# V1_SENSOR.net
KiCad netlist of a schematic drawn in EAGLE
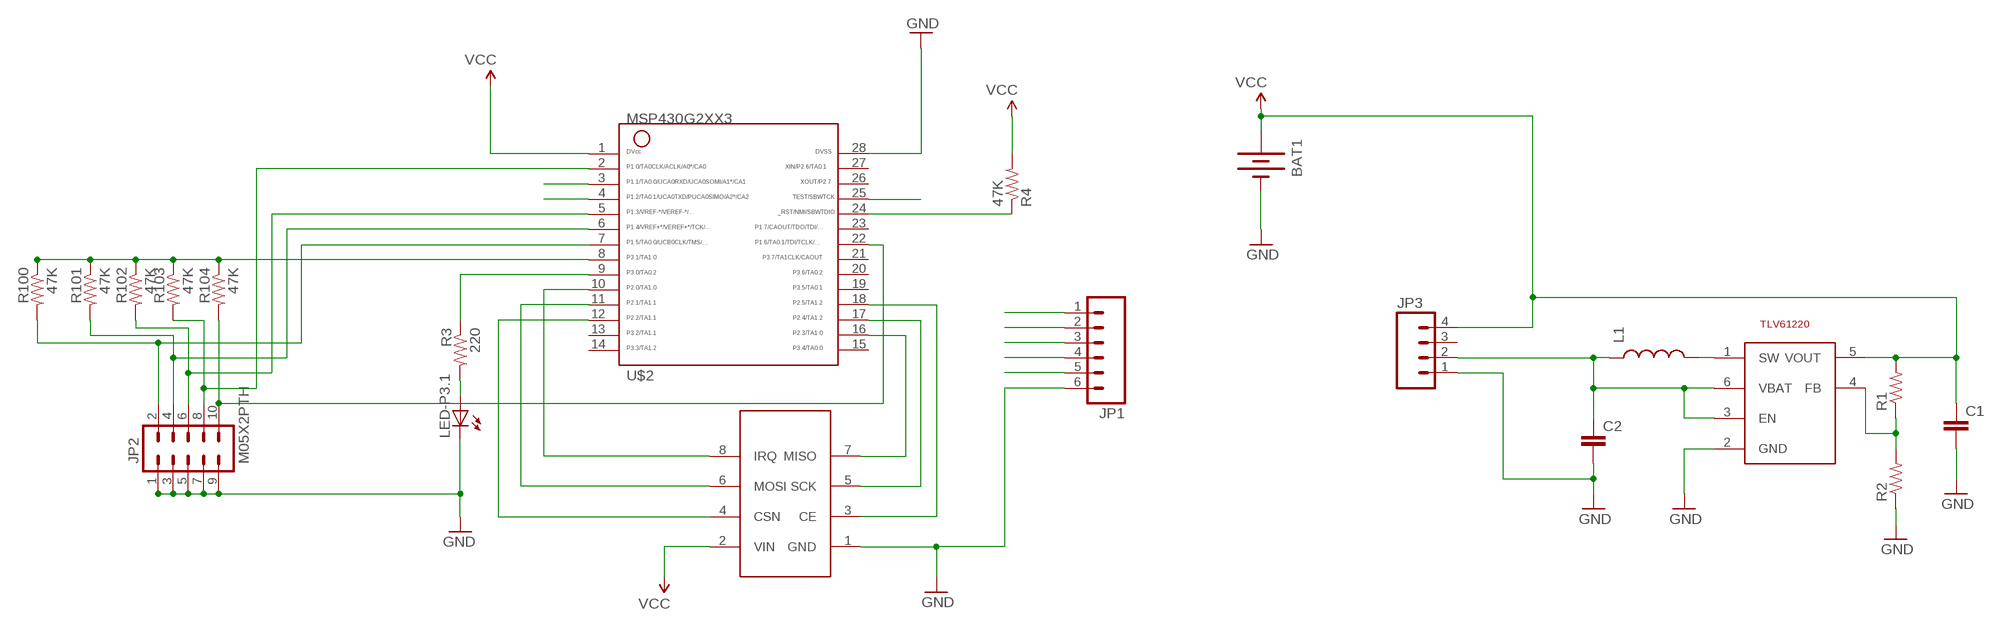
[diagram p0: schematic, sheet 1]

(export (version "E")
  (design (tool "Eeschema 10.0.6"))
  (components
    (comp (ref "BAT1")
      (value "BATTERY20PTH")
      (footprint "eagle-import:BATTCOM_20MM_PTH")
      (libsource (lib "eagle-import") (part "BATTERY20PTH"))
    )
    (comp (ref "C1")
      (value "CAP0805")
      (footprint "eagle-import:0805")
      (libsource (lib "eagle-import") (part "CAP0805"))
    )
    (comp (ref "C2")
      (value "CAP0805")
      (footprint "eagle-import:0805")
      (libsource (lib "eagle-import") (part "CAP0805"))
    )
    (comp (ref "JP1")
      (value "M06LOCK")
      (footprint "eagle-import:1X06_LOCK")
      (libsource (lib "eagle-import") (part "M06LOCK"))
    )
    (comp (ref "JP2")
      (value "M05X2PTH")
      (footprint "eagle-import:AVR_ICSP")
      (libsource (lib "eagle-import") (part "M05X2PTH"))
    )
    (comp (ref "JP3")
      (value "M04LOCK")
      (footprint "eagle-import:1X04_LOCK")
      (libsource (lib "eagle-import") (part "M04LOCK"))
    )
    (comp (ref "L1")
      (value "INDUCTOR0805")
      (footprint "eagle-import:0805")
      (libsource (lib "eagle-import") (part "INDUCTOR0805"))
    )
    (comp (ref "LED-P3.1")
      (value "LED0805")
      (footprint "eagle-import:LED-0805")
      (libsource (lib "eagle-import") (part "LED0805"))
    )
    (comp (ref "R1")
      (value "RESISTOR0805-RES")
      (footprint "eagle-import:0805")
      (libsource (lib "eagle-import") (part "RESISTOR0805-RES"))
    )
    (comp (ref "R2")
      (value "RESISTOR0805-RES")
      (footprint "eagle-import:0805")
      (libsource (lib "eagle-import") (part "RESISTOR0805-RES"))
    )
    (comp (ref "R3")
      (value "220")
      (footprint "eagle-import:0805")
      (libsource (lib "eagle-import") (part "SparkFun-Resistors_RESISTOR0805-RES"))
    )
    (comp (ref "R4")
      (value "47K")
      (footprint "eagle-import:0805")
      (libsource (lib "eagle-import") (part "SparkFun-Resistors_RESISTOR0805-RES"))
    )
    (comp (ref "R100")
      (value "47K")
      (footprint "eagle-import:0805")
      (libsource (lib "eagle-import") (part "SparkFun-Resistors_RESISTOR0805-RES"))
    )
    (comp (ref "R101")
      (value "47K")
      (footprint "eagle-import:0805")
      (libsource (lib "eagle-import") (part "SparkFun-Resistors_RESISTOR0805-RES"))
    )
    (comp (ref "R102")
      (value "47K")
      (footprint "eagle-import:0805")
      (libsource (lib "eagle-import") (part "SparkFun-Resistors_RESISTOR0805-RES"))
    )
    (comp (ref "R103")
      (value "47K")
      (footprint "eagle-import:0805")
      (libsource (lib "eagle-import") (part "SparkFun-Resistors_RESISTOR0805-RES"))
    )
    (comp (ref "R104")
      (value "47K")
      (footprint "eagle-import:0805")
      (libsource (lib "eagle-import") (part "SparkFun-Resistors_RESISTOR0805-RES"))
    )
    (comp (ref "U$1")
      (value "TLV61220")
      (footprint "eagle-import:SOT23-6L")
      (libsource (lib "eagle-import") (part "TI-TLV61220"))
    )
    (comp (ref "U$2")
      (value "MSP430G2553")
      (footprint "eagle-import:PW28")
      (libsource (lib "eagle-import") (part "G2XX3---PW28"))
    )
    (comp (ref "U1")
      (value "NRF24L01-4X2")
      (footprint "eagle-import:NRF24L01-4X2")
      (libsource (lib "eagle-import") (part "NRF24L01-4X2"))
    )
  )
  (nets
    (net (code "1") (name "/RESET") (class "Default")
      (node (ref "JP1") (pin "5") (pinfunction "5_5") (pintype "passive"))
      (node (ref "R4") (pin "1") (pinfunction "1_1") (pintype "passive"))
      (node (ref "U$2") (pin "24") (pinfunction "24_24") (pintype "bidirectional"))
    )
    (net (code "2") (name "/RXD") (class "Default")
      (node (ref "JP1") (pin "2") (pinfunction "2_2") (pintype "passive"))
      (node (ref "U$2") (pin "3") (pinfunction "3_3") (pintype "bidirectional"))
    )
    (net (code "3") (name "/TEST") (class "Default")
      (node (ref "JP1") (pin "4") (pinfunction "4_4") (pintype "passive"))
      (node (ref "U$2") (pin "25") (pinfunction "25_25") (pintype "bidirectional"))
    )
    (net (code "4") (name "/TXD") (class "Default")
      (node (ref "JP1") (pin "3") (pinfunction "3_3") (pintype "passive"))
      (node (ref "U$2") (pin "4") (pinfunction "4_4") (pintype "bidirectional"))
    )
    (net (code "5") (name "GND") (class "Default")
      (node (ref "BAT1") (pin "2") (pinfunction "-_2") (pintype "power_in"))
      (node (ref "C1") (pin "2") (pinfunction "2_2") (pintype "passive"))
      (node (ref "C2") (pin "2") (pinfunction "2_2") (pintype "passive"))
      (node (ref "JP1") (pin "6") (pinfunction "6_6") (pintype "passive"))
      (node (ref "JP2") (pin "1") (pinfunction "1_1") (pintype "passive"))
      (node (ref "JP2") (pin "3") (pinfunction "3_3") (pintype "passive"))
      (node (ref "JP2") (pin "5") (pinfunction "5_5") (pintype "passive"))
      (node (ref "JP2") (pin "7") (pinfunction "7_7") (pintype "passive"))
      (node (ref "JP2") (pin "9") (pinfunction "9_9") (pintype "passive"))
      (node (ref "JP3") (pin "1") (pinfunction "1_1") (pintype "passive"))
      (node (ref "LED-P3.1") (pin "C") (pinfunction "C_C") (pintype "passive"))
      (node (ref "R2") (pin "1") (pinfunction "1_1") (pintype "passive"))
      (node (ref "U$1") (pin "2") (pinfunction "GND_2") (pintype "power_in"))
      (node (ref "U$2") (pin "28") (pinfunction "28_28") (pintype "bidirectional"))
      (node (ref "U1") (pin "1") (pinfunction "GND_1") (pintype "power_in"))
    )
    (net (code "6") (name "Net-(JP2-Pad2)") (class "Default")
      (node (ref "JP2") (pin "2") (pinfunction "2_2") (pintype "passive"))
      (node (ref "R100") (pin "2") (pinfunction "2_2") (pintype "passive"))
      (node (ref "U$2") (pin "7") (pinfunction "7_7") (pintype "bidirectional"))
    )
    (net (code "7") (name "Net-(JP2-Pad4)") (class "Default")
      (node (ref "JP2") (pin "4") (pinfunction "4_4") (pintype "passive"))
      (node (ref "R101") (pin "2") (pinfunction "2_2") (pintype "passive"))
      (node (ref "U$2") (pin "6") (pinfunction "6_6") (pintype "bidirectional"))
    )
    (net (code "8") (name "Net-(JP2-Pad6)") (class "Default")
      (node (ref "JP2") (pin "6") (pinfunction "6_6") (pintype "passive"))
      (node (ref "R102") (pin "2") (pinfunction "2_2") (pintype "passive"))
      (node (ref "U$2") (pin "5") (pinfunction "5_5") (pintype "bidirectional"))
    )
    (net (code "9") (name "Net-(JP2-Pad8)") (class "Default")
      (node (ref "JP2") (pin "8") (pinfunction "8_8") (pintype "passive"))
      (node (ref "R103") (pin "2") (pinfunction "2_2") (pintype "passive"))
      (node (ref "U$2") (pin "2") (pinfunction "2_2") (pintype "bidirectional"))
    )
    (net (code "10") (name "Net-(JP2-Pad10)") (class "Default")
      (node (ref "JP2") (pin "10") (pinfunction "10_10") (pintype "passive"))
      (node (ref "R104") (pin "2") (pinfunction "2_2") (pintype "passive"))
      (node (ref "U$2") (pin "22") (pinfunction "22_22") (pintype "bidirectional"))
    )
    (net (code "11") (name "Net-(LED-P3.1-PadA)") (class "Default")
      (node (ref "LED-P3.1") (pin "A") (pinfunction "A_A") (pintype "passive"))
      (node (ref "R3") (pin "2") (pinfunction "2_2") (pintype "passive"))
    )
    (net (code "12") (name "Net-(R3-Pad1)") (class "Default")
      (node (ref "R3") (pin "1") (pinfunction "1_1") (pintype "passive"))
      (node (ref "U$2") (pin "9") (pinfunction "9_9") (pintype "bidirectional"))
    )
    (net (code "13") (name "Net-(R100-Pad1)") (class "Default")
      (node (ref "R100") (pin "1") (pinfunction "1_1") (pintype "passive"))
      (node (ref "R101") (pin "1") (pinfunction "1_1") (pintype "passive"))
      (node (ref "R102") (pin "1") (pinfunction "1_1") (pintype "passive"))
      (node (ref "R103") (pin "1") (pinfunction "1_1") (pintype "passive"))
      (node (ref "R104") (pin "1") (pinfunction "1_1") (pintype "passive"))
      (node (ref "U$2") (pin "8") (pinfunction "8_8") (pintype "bidirectional"))
    )
    (net (code "14") (name "Net-(U$1-EN)") (class "Default")
      (node (ref "C2") (pin "1") (pinfunction "1_1") (pintype "passive"))
      (node (ref "JP3") (pin "2") (pinfunction "2_2") (pintype "passive"))
      (node (ref "L1") (pin "1") (pinfunction "1_1") (pintype "passive"))
      (node (ref "U$1") (pin "3") (pinfunction "EN_3") (pintype "input"))
      (node (ref "U$1") (pin "6") (pinfunction "VBAT_6") (pintype "power_in"))
    )
    (net (code "15") (name "Net-(U$1-FB)") (class "Default")
      (node (ref "R1") (pin "1") (pinfunction "1_1") (pintype "passive"))
      (node (ref "R2") (pin "2") (pinfunction "2_2") (pintype "passive"))
      (node (ref "U$1") (pin "4") (pinfunction "FB_4") (pintype "input"))
    )
    (net (code "16") (name "Net-(U$1-SW)") (class "Default")
      (node (ref "L1") (pin "2") (pinfunction "2_2") (pintype "passive"))
      (node (ref "U$1") (pin "1") (pinfunction "SW_1") (pintype "power_in"))
    )
    (net (code "17") (name "Net-(U1-CE)") (class "Default")
      (node (ref "U$2") (pin "18") (pinfunction "18_18") (pintype "bidirectional"))
      (node (ref "U1") (pin "3") (pinfunction "CE_3") (pintype "input"))
    )
    (net (code "18") (name "Net-(U1-CSN)") (class "Default")
      (node (ref "U$2") (pin "12") (pinfunction "12_12") (pintype "bidirectional"))
      (node (ref "U1") (pin "4") (pinfunction "CSN_4") (pintype "input"))
    )
    (net (code "19") (name "Net-(U1-IRQ)") (class "Default")
      (node (ref "U$2") (pin "10") (pinfunction "10_10") (pintype "bidirectional"))
      (node (ref "U1") (pin "8") (pinfunction "IRQ_8") (pintype "output"))
    )
    (net (code "20") (name "Net-(U1-MISO)") (class "Default")
      (node (ref "U$2") (pin "16") (pinfunction "16_16") (pintype "bidirectional"))
      (node (ref "U1") (pin "7") (pinfunction "MISO_7") (pintype "output"))
    )
    (net (code "21") (name "Net-(U1-MOSI)") (class "Default")
      (node (ref "U$2") (pin "11") (pinfunction "11_11") (pintype "bidirectional"))
      (node (ref "U1") (pin "6") (pinfunction "MOSI_6") (pintype "input"))
    )
    (net (code "22") (name "Net-(U1-SCK)") (class "Default")
      (node (ref "U$2") (pin "17") (pinfunction "17_17") (pintype "bidirectional"))
      (node (ref "U1") (pin "5") (pinfunction "SCK_5") (pintype "input"))
    )
    (net (code "23") (name "VCC") (class "Default")
      (node (ref "BAT1") (pin "1") (pinfunction "+_1") (pintype "power_in"))
      (node (ref "C1") (pin "1") (pinfunction "1_1") (pintype "passive"))
      (node (ref "JP1") (pin "1") (pinfunction "1_1") (pintype "passive"))
      (node (ref "JP3") (pin "4") (pinfunction "4_4") (pintype "passive"))
      (node (ref "R1") (pin "2") (pinfunction "2_2") (pintype "passive"))
      (node (ref "R4") (pin "2") (pinfunction "2_2") (pintype "passive"))
      (node (ref "U$1") (pin "5") (pinfunction "VOUT_5") (pintype "power_in"))
      (node (ref "U$2") (pin "1") (pinfunction "1_1") (pintype "bidirectional"))
      (node (ref "U1") (pin "2") (pinfunction "VIN_2") (pintype "power_in"))
    )
    (net (code "24") (name "unconnected-(JP3-Pad3)") (class "Default")
      (node (ref "JP3") (pin "3") (pinfunction "3_3") (pintype "passive"))
    )
    (net (code "25") (name "unconnected-(U$2-Pad13)") (class "Default")
      (node (ref "U$2") (pin "13") (pinfunction "13_13") (pintype "bidirectional"))
    )
    (net (code "26") (name "unconnected-(U$2-Pad14)") (class "Default")
      (node (ref "U$2") (pin "14") (pinfunction "14_14") (pintype "bidirectional"))
    )
    (net (code "27") (name "unconnected-(U$2-Pad15)") (class "Default")
      (node (ref "U$2") (pin "15") (pinfunction "15_15") (pintype "bidirectional"))
    )
    (net (code "28") (name "unconnected-(U$2-Pad19)") (class "Default")
      (node (ref "U$2") (pin "19") (pinfunction "19_19") (pintype "bidirectional"))
    )
    (net (code "29") (name "unconnected-(U$2-Pad20)") (class "Default")
      (node (ref "U$2") (pin "20") (pinfunction "20_20") (pintype "bidirectional"))
    )
    (net (code "30") (name "unconnected-(U$2-Pad21)") (class "Default")
      (node (ref "U$2") (pin "21") (pinfunction "21_21") (pintype "bidirectional"))
    )
    (net (code "31") (name "unconnected-(U$2-Pad23)") (class "Default")
      (node (ref "U$2") (pin "23") (pinfunction "23_23") (pintype "bidirectional"))
    )
    (net (code "32") (name "unconnected-(U$2-Pad26)") (class "Default")
      (node (ref "U$2") (pin "26") (pinfunction "26_26") (pintype "bidirectional"))
    )
    (net (code "33") (name "unconnected-(U$2-Pad27)") (class "Default")
      (node (ref "U$2") (pin "27") (pinfunction "27_27") (pintype "bidirectional"))
    )
  )
)
